# CAS_5.net
KiCad netlist of a schematic drawn in Altium Designer
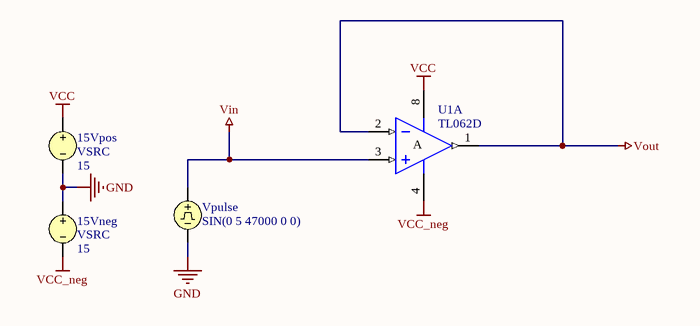
[diagram p0: CAS_5.SchDoc]

(export (version "E")
  (design (tool "Eeschema 10.0.6"))
  (components
    (comp (ref "15Vneg")
      (value "VSRC")
      (description "Voltage Source")
      (fields (field (name "ALTIUM_VALUE") "15") (field (name "PUBLISHER") "Altium Limited"))
      (libsource (lib "Simulation Generic Components") (part "VSRC"))
    )
    (comp (ref "15Vpos")
      (value "VSRC")
      (description "Voltage Source")
      (fields (field (name "ALTIUM_VALUE") "15") (field (name "PUBLISHER") "Altium Limited"))
      (libsource (lib "Simulation Generic Components") (part "VSRC"))
    )
    (comp (ref "U1")
      (value "TL062D")
      (footprint "D008_L")
      (description "Low-Power JFET-Input Operational Amplifier")
      (fields (field (name "PUBLISHER") "Altium Limited"))
      (libsource (lib "TI Operational Amplifier") (part "TL062D"))
    )
    (comp (ref "Vpulse")
      (value "SIN(0 5 47000 0 0)")
      (description "Pulse Voltage Source")
      (fields (field (name "PUBLISHER") "Altium Limited"))
      (libsource (lib "Simulation Sources") (part "VPULSE"))
    )
  )
  (nets
    (net (code "1") (name "GND") (class "Default")
      (node (ref "15Vneg") (pin "1") (pinfunction "1_1") (pintype "passive"))
      (node (ref "15Vpos") (pin "2") (pinfunction "2_2") (pintype "passive"))
      (node (ref "Vpulse") (pin "2") (pinfunction "2_2") (pintype "passive"))
    )
    (net (code "2") (name "VCC") (class "Default")
      (node (ref "15Vpos") (pin "1") (pinfunction "1_1") (pintype "passive"))
      (node (ref "U1") (pin "8") (pinfunction "V+_8") (pintype "power_in"))
    )
    (net (code "3") (name "VCC_neg") (class "Default")
      (node (ref "15Vneg") (pin "2") (pinfunction "2_2") (pintype "passive"))
      (node (ref "U1") (pin "4") (pinfunction "V-_4") (pintype "power_in"))
    )
    (net (code "4") (name "Vin") (class "Default")
      (node (ref "U1") (pin "3") (pinfunction "IN+_3") (pintype "input"))
      (node (ref "Vpulse") (pin "1") (pinfunction "1_1") (pintype "passive"))
    )
    (net (code "5") (name "Vout") (class "Default")
      (node (ref "U1") (pin "1") (pinfunction "OUT_1") (pintype "output"))
      (node (ref "U1") (pin "2") (pinfunction "IN-_2") (pintype "input"))
    )
  )
)
